# User_Interface.net
KiCad netlist of a schematic drawn in Altium Designer
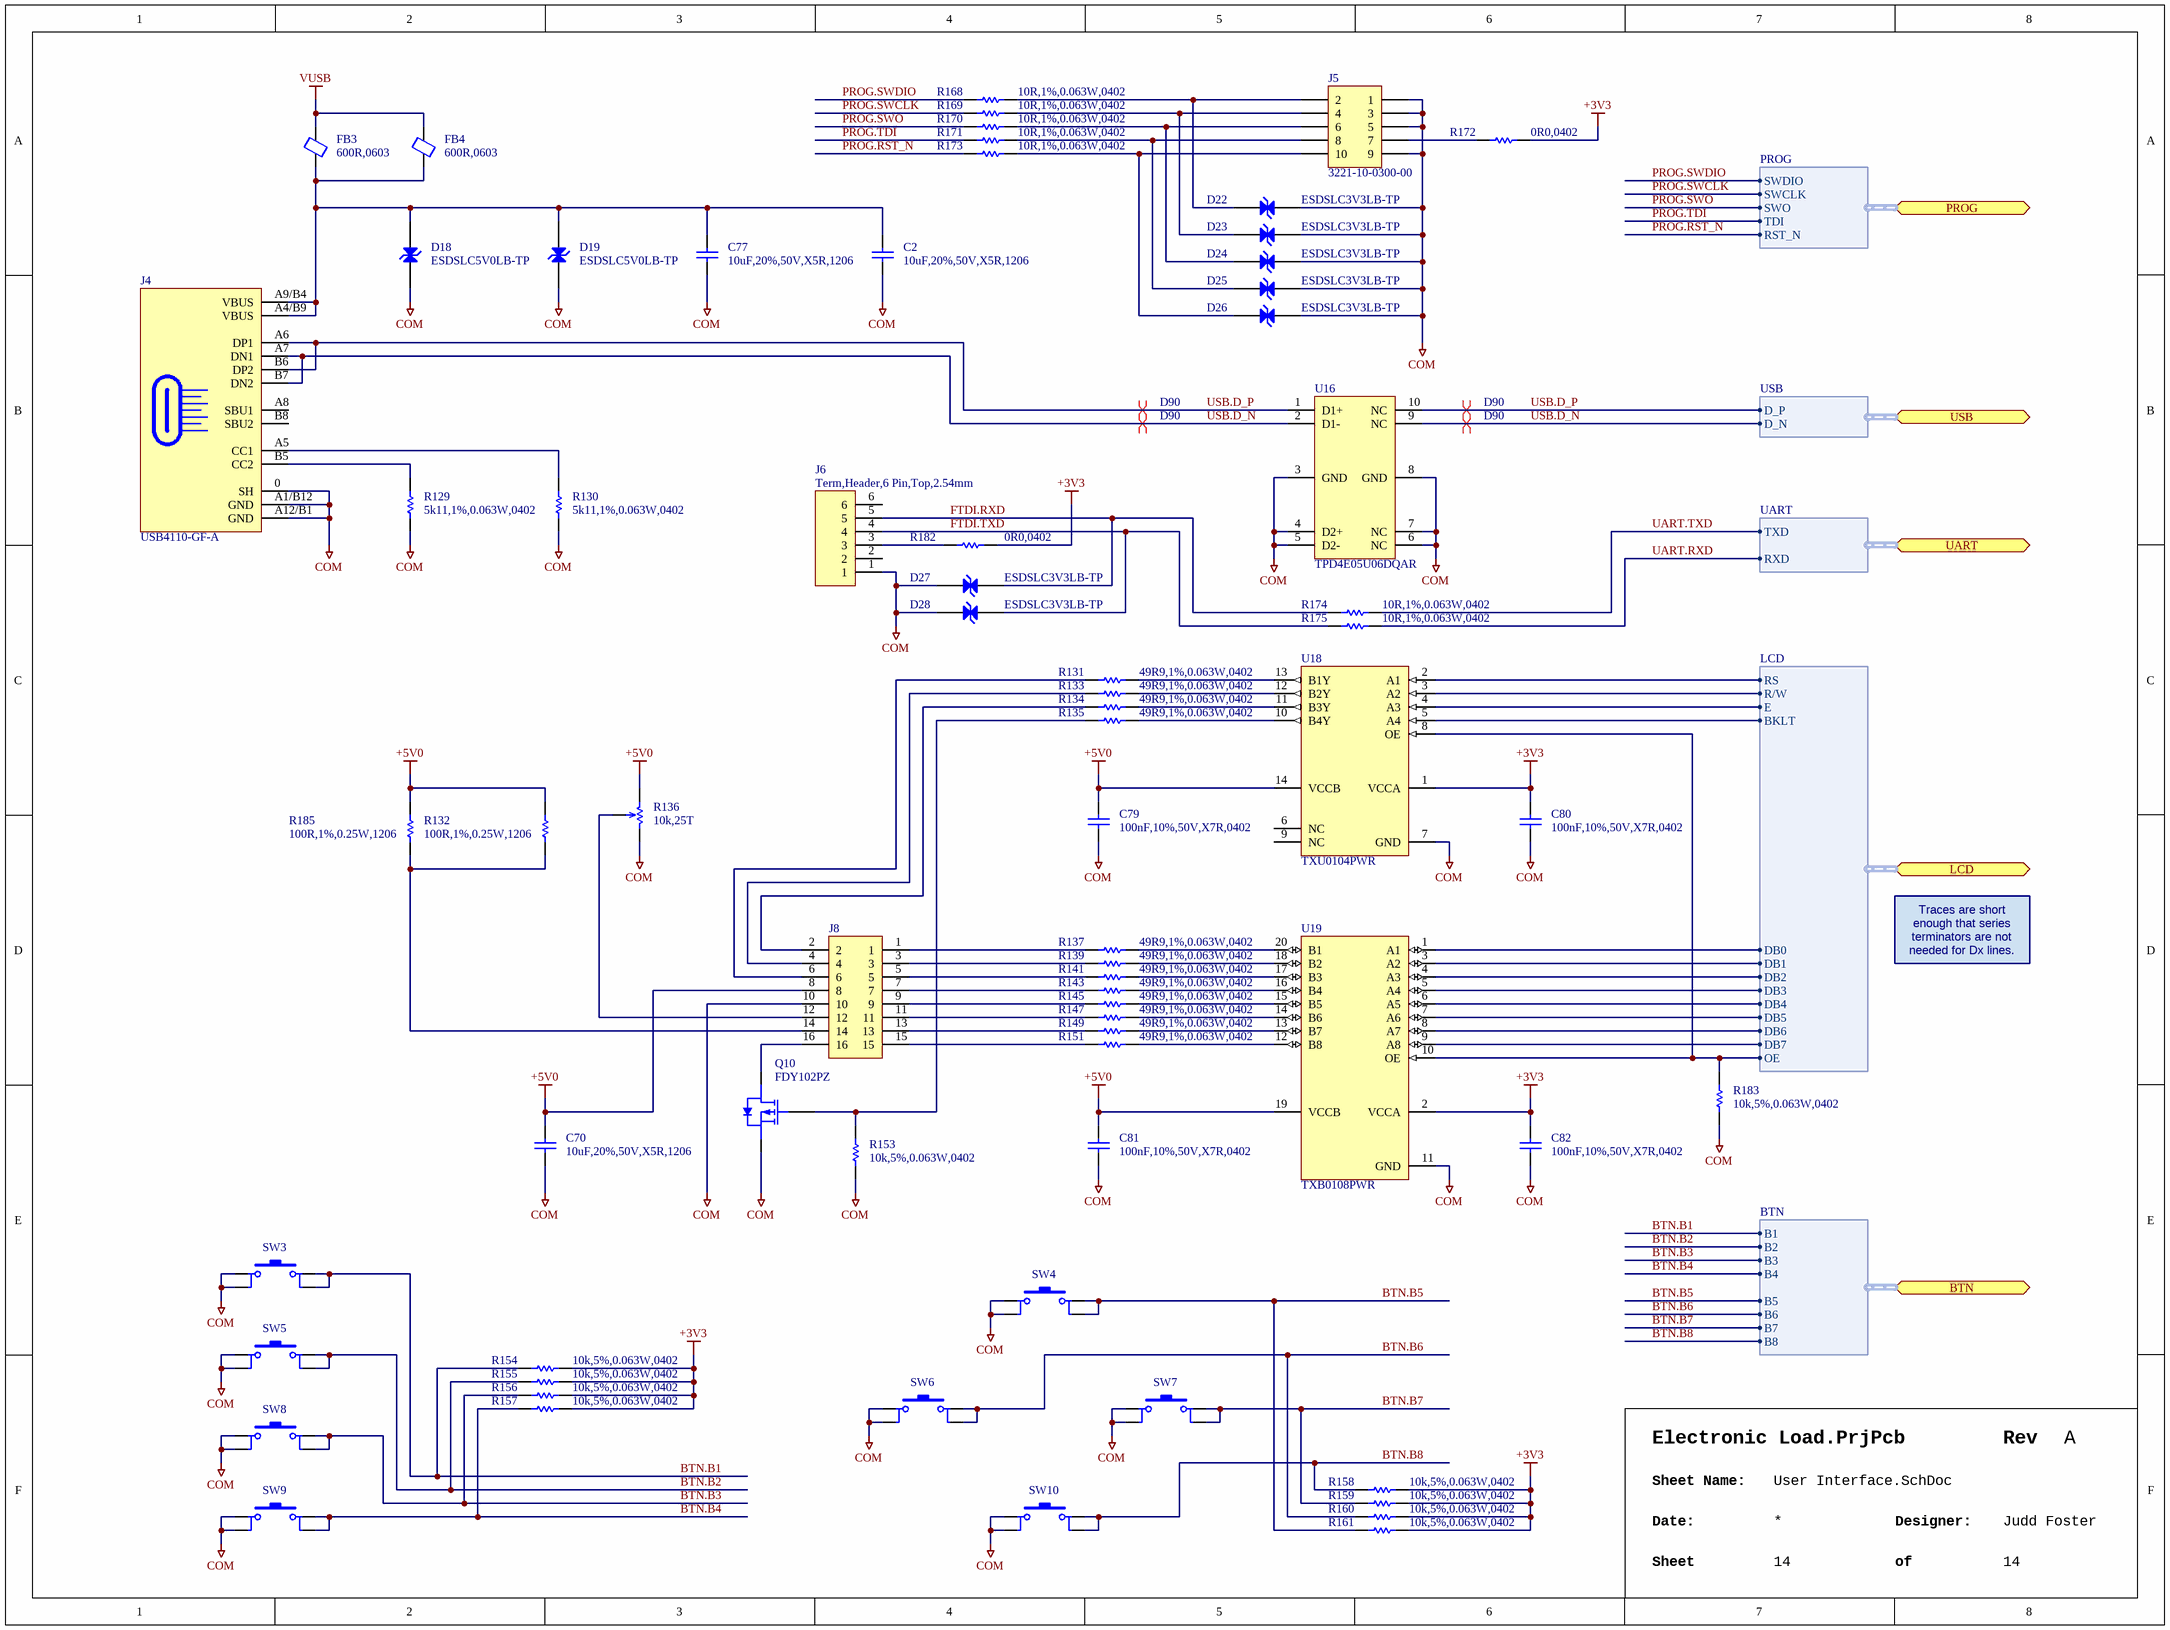
[diagram p0: User Interface.SchDoc]

(export (version "E")
  (design (tool "Eeschema 10.0.6"))
  (components
    (comp (ref "C2")
      (value "10uF,20%,50V,X5R,1206")
      (footprint "CAPC3216X16N")
      (description "10ï¿½F ï¿½20% 50V Ceramic Capacitor X5R 1206 (3216 Metric)")
      (fields
        (field (name "MANUFACTURER 1 PART NUMBER") "CL31A106MBHNNNE")
        (field (name "VENDOR 1 PART NUMBER") "1276-6736-1-ND")
        (field (name "CREATEDBY") "Judd Foster")
      )
      (libsource (lib "Component Library") (part "CAP,Cer,10uF,50VDC,X5R,1206"))
    )
    (comp (ref "C70")
      (value "10uF,20%,50V,X5R,1206")
      (footprint "CAPC3216X16N")
      (description "10ï¿½F ï¿½20% 50V Ceramic Capacitor X5R 1206 (3216 Metric)")
      (fields
        (field (name "MANUFACTURER 1 PART NUMBER") "CL31A106MBHNNNE")
        (field (name "VENDOR 1 PART NUMBER") "1276-6736-1-ND")
        (field (name "CREATEDBY") "Judd Foster")
      )
      (libsource (lib "Component Library") (part "CAP,Cer,10uF,50VDC,X5R,1206"))
    )
    (comp (ref "C77")
      (value "10uF,20%,50V,X5R,1206")
      (footprint "CAPC3216X16N")
      (description "10ï¿½F ï¿½20% 50V Ceramic Capacitor X5R 1206 (3216 Metric)")
      (fields
        (field (name "MANUFACTURER 1 PART NUMBER") "CL31A106MBHNNNE")
        (field (name "VENDOR 1 PART NUMBER") "1276-6736-1-ND")
        (field (name "CREATEDBY") "Judd Foster")
      )
      (libsource (lib "Component Library") (part "CAP,Cer,10uF,50VDC,X5R,1206"))
    )
    (comp (ref "C79")
      (value "100nF,10%,50V,X7R,0402")
      (footprint "CAPC1005X06N")
      (description "50V 100nF X7R Â±10% 0402 Ceramic Capacitors ROHS")
      (fields
        (field (name "MANUFACTURER 1 PART NUMBER") "GRM155R71H104KE14D")
        (field (name "VENDOR 1 PART NUMBER") "C77020")
        (field (name "CREATEDBY") "Judd Foster")
      )
      (libsource (lib "Component Library") (part "CAP,NPOL"))
    )
    (comp (ref "C80")
      (value "100nF,10%,50V,X7R,0402")
      (footprint "CAPC1005X06N")
      (description "50V 100nF X7R Â±10% 0402 Ceramic Capacitors ROHS")
      (fields
        (field (name "MANUFACTURER 1 PART NUMBER") "GRM155R71H104KE14D")
        (field (name "VENDOR 1 PART NUMBER") "C77020")
        (field (name "CREATEDBY") "Judd Foster")
      )
      (libsource (lib "Component Library") (part "CAP,NPOL"))
    )
    (comp (ref "C81")
      (value "100nF,10%,50V,X7R,0402")
      (footprint "CAPC1005X06N")
      (description "50V 100nF X7R Â±10% 0402 Ceramic Capacitors ROHS")
      (fields
        (field (name "MANUFACTURER 1 PART NUMBER") "GRM155R71H104KE14D")
        (field (name "VENDOR 1 PART NUMBER") "C77020")
        (field (name "CREATEDBY") "Judd Foster")
      )
      (libsource (lib "Component Library") (part "CAP,NPOL"))
    )
    (comp (ref "C82")
      (value "100nF,10%,50V,X7R,0402")
      (footprint "CAPC1005X06N")
      (description "50V 100nF X7R Â±10% 0402 Ceramic Capacitors ROHS")
      (fields
        (field (name "MANUFACTURER 1 PART NUMBER") "GRM155R71H104KE14D")
        (field (name "VENDOR 1 PART NUMBER") "C77020")
        (field (name "CREATEDBY") "Judd Foster")
      )
      (libsource (lib "Component Library") (part "CAP,NPOL"))
    )
    (comp (ref "D18")
      (value "ESDSLC5V0LB-TP")
      (footprint "MICROCOMMERCIAL_DFN1006-2_NPOL")
      (description "20V Clamp 4A (8/20ï¿½s) Ipp Tvs Diode Surface Mount 2-DFN1006")
      (fields
        (field (name "VENDOR 1 PART NUMBER") "ESDSLC5V0LB-TPMSCT-ND")
        (field (name "CREATEDBY") "Judd Foster")
      )
      (libsource (lib "Component Library") (part "DIODE,TVS,5.0V,SOD882"))
    )
    (comp (ref "D19")
      (value "ESDSLC5V0LB-TP")
      (footprint "MICROCOMMERCIAL_DFN1006-2_NPOL")
      (description "20V Clamp 4A (8/20ï¿½s) Ipp Tvs Diode Surface Mount 2-DFN1006")
      (fields
        (field (name "VENDOR 1 PART NUMBER") "ESDSLC5V0LB-TPMSCT-ND")
        (field (name "CREATEDBY") "Judd Foster")
      )
      (libsource (lib "Component Library") (part "DIODE,TVS,5.0V,SOD882"))
    )
    (comp (ref "D22")
      (value "ESDSLC3V3LB-TP")
      (footprint "DFN65P100X50-2N")
      (description "20V Clamp 5A (8/20ï¿½s) Ipp Tvs Diode Surface Mount DFN1006-2")
      (fields
        (field (name "VENDOR 1 PART NUMBER") "ESDSLC3V3LB-TPMSCT-ND")
        (field (name "CREATEDBY") "Judd Foster")
      )
      (libsource (lib "Component Library") (part "DIODE,TVS,3.3V,SOD882"))
    )
    (comp (ref "D23")
      (value "ESDSLC3V3LB-TP")
      (footprint "DFN65P100X50-2N")
      (description "20V Clamp 5A (8/20ï¿½s) Ipp Tvs Diode Surface Mount DFN1006-2")
      (fields
        (field (name "VENDOR 1 PART NUMBER") "ESDSLC3V3LB-TPMSCT-ND")
        (field (name "CREATEDBY") "Judd Foster")
      )
      (libsource (lib "Component Library") (part "DIODE,TVS,3.3V,SOD882"))
    )
    (comp (ref "D24")
      (value "ESDSLC3V3LB-TP")
      (footprint "DFN65P100X50-2N")
      (description "20V Clamp 5A (8/20ï¿½s) Ipp Tvs Diode Surface Mount DFN1006-2")
      (fields
        (field (name "VENDOR 1 PART NUMBER") "ESDSLC3V3LB-TPMSCT-ND")
        (field (name "CREATEDBY") "Judd Foster")
      )
      (libsource (lib "Component Library") (part "DIODE,TVS,3.3V,SOD882"))
    )
    (comp (ref "D25")
      (value "ESDSLC3V3LB-TP")
      (footprint "DFN65P100X50-2N")
      (description "20V Clamp 5A (8/20ï¿½s) Ipp Tvs Diode Surface Mount DFN1006-2")
      (fields
        (field (name "VENDOR 1 PART NUMBER") "ESDSLC3V3LB-TPMSCT-ND")
        (field (name "CREATEDBY") "Judd Foster")
      )
      (libsource (lib "Component Library") (part "DIODE,TVS,3.3V,SOD882"))
    )
    (comp (ref "D26")
      (value "ESDSLC3V3LB-TP")
      (footprint "DFN65P100X50-2N")
      (description "20V Clamp 5A (8/20ï¿½s) Ipp Tvs Diode Surface Mount DFN1006-2")
      (fields
        (field (name "VENDOR 1 PART NUMBER") "ESDSLC3V3LB-TPMSCT-ND")
        (field (name "CREATEDBY") "Judd Foster")
      )
      (libsource (lib "Component Library") (part "DIODE,TVS,3.3V,SOD882"))
    )
    (comp (ref "D27")
      (value "ESDSLC3V3LB-TP")
      (footprint "DFN65P100X50-2N")
      (description "20V Clamp 5A (8/20ï¿½s) Ipp Tvs Diode Surface Mount DFN1006-2")
      (fields
        (field (name "VENDOR 1 PART NUMBER") "ESDSLC3V3LB-TPMSCT-ND")
        (field (name "CREATEDBY") "Judd Foster")
      )
      (libsource (lib "Component Library") (part "DIODE,TVS,3.3V,SOD882"))
    )
    (comp (ref "D28")
      (value "ESDSLC3V3LB-TP")
      (footprint "DFN65P100X50-2N")
      (description "20V Clamp 5A (8/20ï¿½s) Ipp Tvs Diode Surface Mount DFN1006-2")
      (fields
        (field (name "VENDOR 1 PART NUMBER") "ESDSLC3V3LB-TPMSCT-ND")
        (field (name "CREATEDBY") "Judd Foster")
      )
      (libsource (lib "Component Library") (part "DIODE,TVS,3.3V,SOD882"))
    )
    (comp (ref "FB3")
      (value "600R,0603")
      (footprint "INDC_0603")
      (description "500mÎ© Â±25% 600Î©@100MHz 0603 Ferrite Beads and Chips ROHS")
      (fields
        (field (name "MANUFACTURER 1 PART NUMBER") "FCM1608KF-601T03")
        (field (name "VENDOR 1 PART NUMBER") "C141723")
        (field (name "CREATEDBY") "Judd Foster")
      )
      (libsource (lib "Component Library") (part "FERRITE"))
    )
    (comp (ref "FB4")
      (value "600R,0603")
      (footprint "INDC_0603")
      (description "500mÎ© Â±25% 600Î©@100MHz 0603 Ferrite Beads and Chips ROHS")
      (fields
        (field (name "MANUFACTURER 1 PART NUMBER") "FCM1608KF-601T03")
        (field (name "VENDOR 1 PART NUMBER") "C141723")
        (field (name "CREATEDBY") "Judd Foster")
      )
      (libsource (lib "Component Library") (part "FERRITE"))
    )
    (comp (ref "J4")
      (value "USB4110-GF-A")
      (footprint "GCT_USB4110-GF-A")
      (fields
        (field (name "VENDOR 1 PART NUMBER") "2073-USB4110-GF-A-1-ND")
        (field (name "CREATEDBY") "Judd Foster")
      )
      (libsource (lib "Component Library") (part "Conn,USB-C,SMD"))
    )
    (comp (ref "J5")
      (value "3221-10-0300-00")
      (footprint "CNC Tech_3221-10-0300-00")
      (description "Connector Header Surface Mount 10 position 0.050\" (1.27mm)")
      (fields (field (name "VENDOR 1 PART NUMBER") "1175-1735-ND") (field (name "CREATEDBY") "Judd Foster"))
      (libsource (lib "Component Library") (part "Term,Header,5x2 Pin,Shroud,1.27mm,SMD"))
    )
    (comp (ref "J6")
      (value "Term,Header,6 Pin,Top,2.54mm")
      (footprint "WURTH_61300611121")
      (description "Connector Header Through Hole 6 position 0.100\" (2.54mm)")
      (fields
        (field (name "MANUFACTURER 1 PART NUMBER") "61300611121")
        (field (name "VENDOR 1 PART NUMBER") "732-5319-ND")
        (field (name "CREATEDBY") "Judd Foster")
      )
      (libsource (lib "Component Library") (part "Term,Header,6 Pin,Top,2.54mm"))
    )
    (comp (ref "J8")
      (value "PPPC082LFBN-RC")
      (footprint "SULLINS_PPPC082LFBN-RC")
      (description "16 Position Header Connector 0.100\" (2.54mm) Through Hole Gold")
      (fields (field (name "VENDOR 1 PART NUMBER") "S7111-ND") (field (name "CREATEDBY") "Judd Foster"))
      (libsource (lib "Component Library") (part "Term,Rcpt,2x8 Pin,2.54mm,Top,Thru"))
    )
    (comp (ref "Q10")
      (value "FDY102PZ")
      (footprint "ONSEMI_SC-89")
      (description "P-Channel 20 V 830mA (Ta) 625mW (Ta) Surface Mount SC-89-3")
      (fields (field (name "VENDOR 1 PART NUMBER") "FDY102PZCT-ND") (field (name "CREATEDBY") "Judd Foster"))
      (libsource (lib "Component Library") (part "MOSFET,P Ch,20V,830mA"))
    )
    (comp (ref "R129")
      (value "5k11,1%,0.063W,0402")
      (footprint "RESC1005X04N")
      (fields
        (field (name "MANUFACTURER 1 PART NUMBER") "AC0402FR-075K11L")
        (field (name "VENDOR 1 PART NUMBER") "13-AC0402FR-075K11LCT-ND")
        (field (name "CREATEDBY") "Judd Foster")
      )
      (libsource (lib "Component Library") (part "RES,5k11,1%,0.063W,0402"))
    )
    (comp (ref "R130")
      (value "5k11,1%,0.063W,0402")
      (footprint "RESC1005X04N")
      (fields
        (field (name "MANUFACTURER 1 PART NUMBER") "AC0402FR-075K11L")
        (field (name "VENDOR 1 PART NUMBER") "13-AC0402FR-075K11LCT-ND")
        (field (name "CREATEDBY") "Judd Foster")
      )
      (libsource (lib "Component Library") (part "RES,5k11,1%,0.063W,0402"))
    )
    (comp (ref "R131")
      (value "49R9,1%,0.063W,0402")
      (footprint "RESC1005X04N")
      (description "49.9 Ohms Â±1% 0.063W, 1/16W Chip Resistor 0402 (1005 Metric) Moisture Resistant Thick Film")
      (fields
        (field (name "MANUFACTURER 1 PART NUMBER") "RC0402FR-0749R9L")
        (field (name "VENDOR 1 PART NUMBER") "311-49.9LRCT-ND")
        (field (name "CREATEDBY") "Judd Foster")
      )
      (libsource (lib "Component Library") (part "RES,49R9,1%,0.063W,0402"))
    )
    (comp (ref "R132")
      (value "100R,1%,0.25W,1206")
      (footprint "SEI_PKG_RMCF1206")
      (description "100 Ohms Â±1% 0.25W, 1/4W Chip Resistor 1206 (3216 Metric) Automotive AEC-Q200 Thick Film")
      (fields
        (field (name "MANUFACTURER 1 PART NUMBER") "RMCF1206FT100R")
        (field (name "VENDOR 1 PART NUMBER") "RMCF1206FT100RCT-ND")
        (field (name "CREATEDBY") "Judd Foster")
      )
      (libsource (lib "Component Library") (part "RES,100R,1%,0.25W,1206"))
    )
    (comp (ref "R133")
      (value "49R9,1%,0.063W,0402")
      (footprint "RESC1005X04N")
      (description "49.9 Ohms Â±1% 0.063W, 1/16W Chip Resistor 0402 (1005 Metric) Moisture Resistant Thick Film")
      (fields
        (field (name "MANUFACTURER 1 PART NUMBER") "RC0402FR-0749R9L")
        (field (name "VENDOR 1 PART NUMBER") "311-49.9LRCT-ND")
        (field (name "CREATEDBY") "Judd Foster")
      )
      (libsource (lib "Component Library") (part "RES,49R9,1%,0.063W,0402"))
    )
    (comp (ref "R134")
      (value "49R9,1%,0.063W,0402")
      (footprint "RESC1005X04N")
      (description "49.9 Ohms Â±1% 0.063W, 1/16W Chip Resistor 0402 (1005 Metric) Moisture Resistant Thick Film")
      (fields
        (field (name "MANUFACTURER 1 PART NUMBER") "RC0402FR-0749R9L")
        (field (name "VENDOR 1 PART NUMBER") "311-49.9LRCT-ND")
        (field (name "CREATEDBY") "Judd Foster")
      )
      (libsource (lib "Component Library") (part "RES,49R9,1%,0.063W,0402"))
    )
    (comp (ref "R135")
      (value "49R9,1%,0.063W,0402")
      (footprint "RESC1005X04N")
      (description "49.9 Ohms Â±1% 0.063W, 1/16W Chip Resistor 0402 (1005 Metric) Moisture Resistant Thick Film")
      (fields
        (field (name "MANUFACTURER 1 PART NUMBER") "RC0402FR-0749R9L")
        (field (name "VENDOR 1 PART NUMBER") "311-49.9LRCT-ND")
        (field (name "CREATEDBY") "Judd Foster")
      )
      (libsource (lib "Component Library") (part "RES,49R9,1%,0.063W,0402"))
    )
    (comp (ref "R136")
      (value "10k,25T")
      (footprint "BOURNS_3296W")
      (description "Â±10% Â±100ppm/â„ƒ 500mW 10kÎ© SIP-3P,9.5x4.8mm Trimmer Potentiometers ROHS")
      (fields
        (field (name "MANUFACTURER 1 PART NUMBER") "3296W-1-103LF")
        (field (name "VENDOR 1 PART NUMBER") "C34846")
        (field (name "CREATEDBY") "Judd Foster")
      )
      (libsource (lib "Component Library") (part "RES,TRIM"))
    )
    (comp (ref "R137")
      (value "49R9,1%,0.063W,0402")
      (footprint "RESC1005X04N")
      (description "49.9 Ohms Â±1% 0.063W, 1/16W Chip Resistor 0402 (1005 Metric) Moisture Resistant Thick Film")
      (fields
        (field (name "MANUFACTURER 1 PART NUMBER") "RC0402FR-0749R9L")
        (field (name "VENDOR 1 PART NUMBER") "311-49.9LRCT-ND")
        (field (name "CREATEDBY") "Judd Foster")
      )
      (libsource (lib "Component Library") (part "RES,49R9,1%,0.063W,0402"))
    )
    (comp (ref "R139")
      (value "49R9,1%,0.063W,0402")
      (footprint "RESC1005X04N")
      (description "49.9 Ohms Â±1% 0.063W, 1/16W Chip Resistor 0402 (1005 Metric) Moisture Resistant Thick Film")
      (fields
        (field (name "MANUFACTURER 1 PART NUMBER") "RC0402FR-0749R9L")
        (field (name "VENDOR 1 PART NUMBER") "311-49.9LRCT-ND")
        (field (name "CREATEDBY") "Judd Foster")
      )
      (libsource (lib "Component Library") (part "RES,49R9,1%,0.063W,0402"))
    )
    (comp (ref "R141")
      (value "49R9,1%,0.063W,0402")
      (footprint "RESC1005X04N")
      (description "49.9 Ohms Â±1% 0.063W, 1/16W Chip Resistor 0402 (1005 Metric) Moisture Resistant Thick Film")
      (fields
        (field (name "MANUFACTURER 1 PART NUMBER") "RC0402FR-0749R9L")
        (field (name "VENDOR 1 PART NUMBER") "311-49.9LRCT-ND")
        (field (name "CREATEDBY") "Judd Foster")
      )
      (libsource (lib "Component Library") (part "RES,49R9,1%,0.063W,0402"))
    )
    (comp (ref "R143")
      (value "49R9,1%,0.063W,0402")
      (footprint "RESC1005X04N")
      (description "49.9 Ohms Â±1% 0.063W, 1/16W Chip Resistor 0402 (1005 Metric) Moisture Resistant Thick Film")
      (fields
        (field (name "MANUFACTURER 1 PART NUMBER") "RC0402FR-0749R9L")
        (field (name "VENDOR 1 PART NUMBER") "311-49.9LRCT-ND")
        (field (name "CREATEDBY") "Judd Foster")
      )
      (libsource (lib "Component Library") (part "RES,49R9,1%,0.063W,0402"))
    )
    (comp (ref "R145")
      (value "49R9,1%,0.063W,0402")
      (footprint "RESC1005X04N")
      (description "49.9 Ohms Â±1% 0.063W, 1/16W Chip Resistor 0402 (1005 Metric) Moisture Resistant Thick Film")
      (fields
        (field (name "MANUFACTURER 1 PART NUMBER") "RC0402FR-0749R9L")
        (field (name "VENDOR 1 PART NUMBER") "311-49.9LRCT-ND")
        (field (name "CREATEDBY") "Judd Foster")
      )
      (libsource (lib "Component Library") (part "RES,49R9,1%,0.063W,0402"))
    )
    (comp (ref "R147")
      (value "49R9,1%,0.063W,0402")
      (footprint "RESC1005X04N")
      (description "49.9 Ohms Â±1% 0.063W, 1/16W Chip Resistor 0402 (1005 Metric) Moisture Resistant Thick Film")
      (fields
        (field (name "MANUFACTURER 1 PART NUMBER") "RC0402FR-0749R9L")
        (field (name "VENDOR 1 PART NUMBER") "311-49.9LRCT-ND")
        (field (name "CREATEDBY") "Judd Foster")
      )
      (libsource (lib "Component Library") (part "RES,49R9,1%,0.063W,0402"))
    )
    (comp (ref "R149")
      (value "49R9,1%,0.063W,0402")
      (footprint "RESC1005X04N")
      (description "49.9 Ohms Â±1% 0.063W, 1/16W Chip Resistor 0402 (1005 Metric) Moisture Resistant Thick Film")
      (fields
        (field (name "MANUFACTURER 1 PART NUMBER") "RC0402FR-0749R9L")
        (field (name "VENDOR 1 PART NUMBER") "311-49.9LRCT-ND")
        (field (name "CREATEDBY") "Judd Foster")
      )
      (libsource (lib "Component Library") (part "RES,49R9,1%,0.063W,0402"))
    )
    (comp (ref "R151")
      (value "49R9,1%,0.063W,0402")
      (footprint "RESC1005X04N")
      (description "49.9 Ohms Â±1% 0.063W, 1/16W Chip Resistor 0402 (1005 Metric) Moisture Resistant Thick Film")
      (fields
        (field (name "MANUFACTURER 1 PART NUMBER") "RC0402FR-0749R9L")
        (field (name "VENDOR 1 PART NUMBER") "311-49.9LRCT-ND")
        (field (name "CREATEDBY") "Judd Foster")
      )
      (libsource (lib "Component Library") (part "RES,49R9,1%,0.063W,0402"))
    )
    (comp (ref "R153")
      (value "10k,5%,0.063W,0402")
      (footprint "RESC1005X04N")
      (description "10 kOhms ï¿½5% 0.063W, 1/16W Chip Resistor 0402 (1005 Metric) Automotive AEC-Q200 Thick Film")
      (fields
        (field (name "MANUFACTURER 1 PART NUMBER") "RMCF0402JT10K0")
        (field (name "VENDOR 1 PART NUMBER") "RMCF0402JT10K0CT-ND")
        (field (name "CREATEDBY") "Judd Foster")
      )
      (libsource (lib "Component Library") (part "RES,10k,5%,0.063W,0402"))
    )
    (comp (ref "R154")
      (value "10k,5%,0.063W,0402")
      (footprint "RESC1005X04N")
      (description "10 kOhms ï¿½5% 0.063W, 1/16W Chip Resistor 0402 (1005 Metric) Automotive AEC-Q200 Thick Film")
      (fields
        (field (name "MANUFACTURER 1 PART NUMBER") "RMCF0402JT10K0")
        (field (name "VENDOR 1 PART NUMBER") "RMCF0402JT10K0CT-ND")
        (field (name "CREATEDBY") "Judd Foster")
      )
      (libsource (lib "Component Library") (part "RES,10k,5%,0.063W,0402"))
    )
    (comp (ref "R155")
      (value "10k,5%,0.063W,0402")
      (footprint "RESC1005X04N")
      (description "10 kOhms ï¿½5% 0.063W, 1/16W Chip Resistor 0402 (1005 Metric) Automotive AEC-Q200 Thick Film")
      (fields
        (field (name "MANUFACTURER 1 PART NUMBER") "RMCF0402JT10K0")
        (field (name "VENDOR 1 PART NUMBER") "RMCF0402JT10K0CT-ND")
        (field (name "CREATEDBY") "Judd Foster")
      )
      (libsource (lib "Component Library") (part "RES,10k,5%,0.063W,0402"))
    )
    (comp (ref "R156")
      (value "10k,5%,0.063W,0402")
      (footprint "RESC1005X04N")
      (description "10 kOhms ï¿½5% 0.063W, 1/16W Chip Resistor 0402 (1005 Metric) Automotive AEC-Q200 Thick Film")
      (fields
        (field (name "MANUFACTURER 1 PART NUMBER") "RMCF0402JT10K0")
        (field (name "VENDOR 1 PART NUMBER") "RMCF0402JT10K0CT-ND")
        (field (name "CREATEDBY") "Judd Foster")
      )
      (libsource (lib "Component Library") (part "RES,10k,5%,0.063W,0402"))
    )
    (comp (ref "R157")
      (value "10k,5%,0.063W,0402")
      (footprint "RESC1005X04N")
      (description "10 kOhms ï¿½5% 0.063W, 1/16W Chip Resistor 0402 (1005 Metric) Automotive AEC-Q200 Thick Film")
      (fields
        (field (name "MANUFACTURER 1 PART NUMBER") "RMCF0402JT10K0")
        (field (name "VENDOR 1 PART NUMBER") "RMCF0402JT10K0CT-ND")
        (field (name "CREATEDBY") "Judd Foster")
      )
      (libsource (lib "Component Library") (part "RES,10k,5%,0.063W,0402"))
    )
    (comp (ref "R158")
      (value "10k,5%,0.063W,0402")
      (footprint "RESC1005X04N")
      (description "10 kOhms ï¿½5% 0.063W, 1/16W Chip Resistor 0402 (1005 Metric) Automotive AEC-Q200 Thick Film")
      (fields
        (field (name "MANUFACTURER 1 PART NUMBER") "RMCF0402JT10K0")
        (field (name "VENDOR 1 PART NUMBER") "RMCF0402JT10K0CT-ND")
        (field (name "CREATEDBY") "Judd Foster")
      )
      (libsource (lib "Component Library") (part "RES,10k,5%,0.063W,0402"))
    )
    (comp (ref "R159")
      (value "10k,5%,0.063W,0402")
      (footprint "RESC1005X04N")
      (description "10 kOhms ï¿½5% 0.063W, 1/16W Chip Resistor 0402 (1005 Metric) Automotive AEC-Q200 Thick Film")
      (fields
        (field (name "MANUFACTURER 1 PART NUMBER") "RMCF0402JT10K0")
        (field (name "VENDOR 1 PART NUMBER") "RMCF0402JT10K0CT-ND")
        (field (name "CREATEDBY") "Judd Foster")
      )
      (libsource (lib "Component Library") (part "RES,10k,5%,0.063W,0402"))
    )
    (comp (ref "R160")
      (value "10k,5%,0.063W,0402")
      (footprint "RESC1005X04N")
      (description "10 kOhms ï¿½5% 0.063W, 1/16W Chip Resistor 0402 (1005 Metric) Automotive AEC-Q200 Thick Film")
      (fields
        (field (name "MANUFACTURER 1 PART NUMBER") "RMCF0402JT10K0")
        (field (name "VENDOR 1 PART NUMBER") "RMCF0402JT10K0CT-ND")
        (field (name "CREATEDBY") "Judd Foster")
      )
      (libsource (lib "Component Library") (part "RES,10k,5%,0.063W,0402"))
    )
    (comp (ref "R161")
      (value "10k,5%,0.063W,0402")
      (footprint "RESC1005X04N")
      (description "10 kOhms ï¿½5% 0.063W, 1/16W Chip Resistor 0402 (1005 Metric) Automotive AEC-Q200 Thick Film")
      (fields
        (field (name "MANUFACTURER 1 PART NUMBER") "RMCF0402JT10K0")
        (field (name "VENDOR 1 PART NUMBER") "RMCF0402JT10K0CT-ND")
        (field (name "CREATEDBY") "Judd Foster")
      )
      (libsource (lib "Component Library") (part "RES,10k,5%,0.063W,0402"))
    )
    (comp (ref "R168")
      (value "10R,1%,0.063W,0402")
      (footprint "RESC1005X04N")
      (description "10 Ohms ï¿½1% 0.063W, 1/16W Chip Resistor 0402 (1005 Metric) Automotive AEC-Q200 Thick Film")
      (fields
        (field (name "MANUFACTURER 1 PART NUMBER") "ERJ-2RKF10R0X")
        (field (name "VENDOR 1 PART NUMBER") "P10.0LCT-ND")
        (field (name "CREATEDBY") "Judd Foster")
      )
      (libsource (lib "Component Library") (part "RES,10R,1%,0.063W,0402"))
    )
    (comp (ref "R169")
      (value "10R,1%,0.063W,0402")
      (footprint "RESC1005X04N")
      (description "10 Ohms ï¿½1% 0.063W, 1/16W Chip Resistor 0402 (1005 Metric) Automotive AEC-Q200 Thick Film")
      (fields
        (field (name "MANUFACTURER 1 PART NUMBER") "ERJ-2RKF10R0X")
        (field (name "VENDOR 1 PART NUMBER") "P10.0LCT-ND")
        (field (name "CREATEDBY") "Judd Foster")
      )
      (libsource (lib "Component Library") (part "RES,10R,1%,0.063W,0402"))
    )
    (comp (ref "R170")
      (value "10R,1%,0.063W,0402")
      (footprint "RESC1005X04N")
      (description "10 Ohms ï¿½1% 0.063W, 1/16W Chip Resistor 0402 (1005 Metric) Automotive AEC-Q200 Thick Film")
      (fields
        (field (name "MANUFACTURER 1 PART NUMBER") "ERJ-2RKF10R0X")
        (field (name "VENDOR 1 PART NUMBER") "P10.0LCT-ND")
        (field (name "CREATEDBY") "Judd Foster")
      )
      (libsource (lib "Component Library") (part "RES,10R,1%,0.063W,0402"))
    )
    (comp (ref "R171")
      (value "10R,1%,0.063W,0402")
      (footprint "RESC1005X04N")
      (description "10 Ohms ï¿½1% 0.063W, 1/16W Chip Resistor 0402 (1005 Metric) Automotive AEC-Q200 Thick Film")
      (fields
        (field (name "MANUFACTURER 1 PART NUMBER") "ERJ-2RKF10R0X")
        (field (name "VENDOR 1 PART NUMBER") "P10.0LCT-ND")
        (field (name "CREATEDBY") "Judd Foster")
      )
      (libsource (lib "Component Library") (part "RES,10R,1%,0.063W,0402"))
    )
    (comp (ref "R172")
      (value "0R0,0402")
      (footprint "RESC1005X04N")
      (description "0 Ohms Jumper 0.1W, 1/10W Chip Resistor 0402 (1005 Metric) Automotive AEC-Q200 Thick Film")
      (fields
        (field (name "MANUFACTURER 1 PART NUMBER") "ERJ-2GE0R00X")
        (field (name "VENDOR 1 PART NUMBER") "P0.0JCT-ND")
        (field (name "CREATEDBY") "Judd Foster")
      )
      (libsource (lib "Component Library") (part "RES,0R0,0402"))
    )
    (comp (ref "R173")
      (value "10R,1%,0.063W,0402")
      (footprint "RESC1005X04N")
      (description "10 Ohms ï¿½1% 0.063W, 1/16W Chip Resistor 0402 (1005 Metric) Automotive AEC-Q200 Thick Film")
      (fields
        (field (name "MANUFACTURER 1 PART NUMBER") "ERJ-2RKF10R0X")
        (field (name "VENDOR 1 PART NUMBER") "P10.0LCT-ND")
        (field (name "CREATEDBY") "Judd Foster")
      )
      (libsource (lib "Component Library") (part "RES,10R,1%,0.063W,0402"))
    )
    (comp (ref "R174")
      (value "10R,1%,0.063W,0402")
      (footprint "RESC1005X04N")
      (description "10 Ohms ï¿½1% 0.063W, 1/16W Chip Resistor 0402 (1005 Metric) Automotive AEC-Q200 Thick Film")
      (fields
        (field (name "MANUFACTURER 1 PART NUMBER") "ERJ-2RKF10R0X")
        (field (name "VENDOR 1 PART NUMBER") "P10.0LCT-ND")
        (field (name "CREATEDBY") "Judd Foster")
      )
      (libsource (lib "Component Library") (part "RES,10R,1%,0.063W,0402"))
    )
    (comp (ref "R175")
      (value "10R,1%,0.063W,0402")
      (footprint "RESC1005X04N")
      (description "10 Ohms ï¿½1% 0.063W, 1/16W Chip Resistor 0402 (1005 Metric) Automotive AEC-Q200 Thick Film")
      (fields
        (field (name "MANUFACTURER 1 PART NUMBER") "ERJ-2RKF10R0X")
        (field (name "VENDOR 1 PART NUMBER") "P10.0LCT-ND")
        (field (name "CREATEDBY") "Judd Foster")
      )
      (libsource (lib "Component Library") (part "RES,10R,1%,0.063W,0402"))
    )
    (comp (ref "R182")
      (value "0R0,0402")
      (footprint "RESC1005X04N")
      (description "0 Ohms Jumper 0.1W, 1/10W Chip Resistor 0402 (1005 Metric) Automotive AEC-Q200 Thick Film")
      (fields
        (field (name "MANUFACTURER 1 PART NUMBER") "ERJ-2GE0R00X")
        (field (name "VENDOR 1 PART NUMBER") "P0.0JCT-ND")
        (field (name "CREATEDBY") "Judd Foster")
      )
      (libsource (lib "Component Library") (part "RES,0R0,0402"))
    )
    (comp (ref "R183")
      (value "10k,5%,0.063W,0402")
      (footprint "RESC1005X04N")
      (description "10 kOhms ï¿½5% 0.063W, 1/16W Chip Resistor 0402 (1005 Metric) Automotive AEC-Q200 Thick Film")
      (fields
        (field (name "MANUFACTURER 1 PART NUMBER") "RMCF0402JT10K0")
        (field (name "VENDOR 1 PART NUMBER") "RMCF0402JT10K0CT-ND")
        (field (name "CREATEDBY") "Judd Foster")
      )
      (libsource (lib "Component Library") (part "RES,10k,5%,0.063W,0402"))
    )
    (comp (ref "R185")
      (value "100R,1%,0.25W,1206")
      (footprint "SEI_PKG_RMCF1206")
      (description "100 Ohms Â±1% 0.25W, 1/4W Chip Resistor 1206 (3216 Metric) Automotive AEC-Q200 Thick Film")
      (fields
        (field (name "MANUFACTURER 1 PART NUMBER") "RMCF1206FT100R")
        (field (name "VENDOR 1 PART NUMBER") "RMCF1206FT100RCT-ND")
        (field (name "CREATEDBY") "Judd Foster")
      )
      (libsource (lib "Component Library") (part "RES,100R,1%,0.25W,1206"))
    )
    (comp (ref "SW3")
      (value "PTS645SK43SMTR92 LFS")
      (footprint "C&K_PTS645SK43SMTR92 LFS")
      (description "Tactile Switch SPST-NO Top Actuated Surface Mount")
      (fields (field (name "VENDOR 1 PART NUMBER") "CKN9084CT-ND") (field (name "CREATEDBY") "Judd Foster"))
      (libsource (lib "Component Library") (part "Switch,Tactile,SPST-NO,SMD,H4.3"))
    )
    (comp (ref "SW4")
      (value "PTS645SK43SMTR92 LFS")
      (footprint "C&K_PTS645SK43SMTR92 LFS")
      (description "Tactile Switch SPST-NO Top Actuated Surface Mount")
      (fields (field (name "VENDOR 1 PART NUMBER") "CKN9084CT-ND") (field (name "CREATEDBY") "Judd Foster"))
      (libsource (lib "Component Library") (part "Switch,Tactile,SPST-NO,SMD,H4.3"))
    )
    (comp (ref "SW5")
      (value "PTS645SK43SMTR92 LFS")
      (footprint "C&K_PTS645SK43SMTR92 LFS")
      (description "Tactile Switch SPST-NO Top Actuated Surface Mount")
      (fields (field (name "VENDOR 1 PART NUMBER") "CKN9084CT-ND") (field (name "CREATEDBY") "Judd Foster"))
      (libsource (lib "Component Library") (part "Switch,Tactile,SPST-NO,SMD,H4.3"))
    )
    (comp (ref "SW6")
      (value "PTS645SK43SMTR92 LFS")
      (footprint "C&K_PTS645SK43SMTR92 LFS")
      (description "Tactile Switch SPST-NO Top Actuated Surface Mount")
      (fields (field (name "VENDOR 1 PART NUMBER") "CKN9084CT-ND") (field (name "CREATEDBY") "Judd Foster"))
      (libsource (lib "Component Library") (part "Switch,Tactile,SPST-NO,SMD,H4.3"))
    )
    (comp (ref "SW7")
      (value "PTS645SK43SMTR92 LFS")
      (footprint "C&K_PTS645SK43SMTR92 LFS")
      (description "Tactile Switch SPST-NO Top Actuated Surface Mount")
      (fields (field (name "VENDOR 1 PART NUMBER") "CKN9084CT-ND") (field (name "CREATEDBY") "Judd Foster"))
      (libsource (lib "Component Library") (part "Switch,Tactile,SPST-NO,SMD,H4.3"))
    )
    (comp (ref "SW8")
      (value "PTS645SK43SMTR92 LFS")
      (footprint "C&K_PTS645SK43SMTR92 LFS")
      (description "Tactile Switch SPST-NO Top Actuated Surface Mount")
      (fields (field (name "VENDOR 1 PART NUMBER") "CKN9084CT-ND") (field (name "CREATEDBY") "Judd Foster"))
      (libsource (lib "Component Library") (part "Switch,Tactile,SPST-NO,SMD,H4.3"))
    )
    (comp (ref "SW9")
      (value "PTS645SK43SMTR92 LFS")
      (footprint "C&K_PTS645SK43SMTR92 LFS")
      (description "Tactile Switch SPST-NO Top Actuated Surface Mount")
      (fields (field (name "VENDOR 1 PART NUMBER") "CKN9084CT-ND") (field (name "CREATEDBY") "Judd Foster"))
      (libsource (lib "Component Library") (part "Switch,Tactile,SPST-NO,SMD,H4.3"))
    )
    (comp (ref "SW10")
      (value "PTS645SK43SMTR92 LFS")
      (footprint "C&K_PTS645SK43SMTR92 LFS")
      (description "Tactile Switch SPST-NO Top Actuated Surface Mount")
      (fields (field (name "VENDOR 1 PART NUMBER") "CKN9084CT-ND") (field (name "CREATEDBY") "Judd Foster"))
      (libsource (lib "Component Library") (part "Switch,Tactile,SPST-NO,SMD,H4.3"))
    )
    (comp (ref "U16")
      (value "TPD4E05U06DQAR")
      (footprint "TEXASINSTRUMENTS_PKG_DQA0009A")
      (description "2.5A@8/20us 14V 40W@8/20us 6.5V Unidirectional 5.5V USON-10(1x2.5) TVS Diodes ROHS")
      (fields (field (name "VENDOR 1 PART NUMBER") "C138714") (field (name "CREATEDBY") "Judd Foster"))
      (libsource (lib "Component Library") (part "TPD4E05U06DQAR"))
    )
    (comp (ref "U18")
      (value "TXU0104PWR")
      (footprint "SOP65P640X120-14N")
      (description "General Purpose Amplifier Circuit Rail-to-Rail 8-VSSOP")
      (fields
        (field (name "VENDOR 1 PART NUMBER") "296-TXU0104PWRCT-ND")
        (field (name "CREATEDBY") "Judd Foster")
      )
      (libsource (lib "Component Library") (part "TXU0104PWR"))
    )
    (comp (ref "U19")
      (value "TXB0108PWR")
      (footprint "TEXASINSTRUMENTS_PKG_PW0020A")
      (description "100Mbps 1 8 TSSOP-20 Translators, Level Shifters ROHS")
      (fields (field (name "VENDOR 1 PART NUMBER") "C53406") (field (name "CREATEDBY") "Judd Foster"))
      (libsource (lib "Component Library") (part "TXB0108PWR"))
    )
  )
  (nets
    (net (code "6") (name "+3V3") (class "Default")
      (node (ref "C80") (pin "2") (pinfunction "2_2") (pintype "passive"))
      (node (ref "C82") (pin "2") (pinfunction "2_2") (pintype "passive"))
      (node (ref "R154") (pin "2") (pinfunction "2_2") (pintype "passive"))
      (node (ref "R155") (pin "2") (pinfunction "2_2") (pintype "passive"))
      (node (ref "R156") (pin "2") (pinfunction "2_2") (pintype "passive"))
      (node (ref "R157") (pin "2") (pinfunction "2_2") (pintype "passive"))
      (node (ref "R158") (pin "2") (pinfunction "2_2") (pintype "passive"))
      (node (ref "R159") (pin "2") (pinfunction "2_2") (pintype "passive"))
      (node (ref "R160") (pin "2") (pinfunction "2_2") (pintype "passive"))
      (node (ref "R161") (pin "2") (pinfunction "2_2") (pintype "passive"))
      (node (ref "R172") (pin "2") (pinfunction "2_2") (pintype "passive"))
      (node (ref "R182") (pin "2") (pinfunction "2_2") (pintype "passive"))
      (node (ref "U18") (pin "1") (pinfunction "VCCA_1") (pintype "power_in"))
      (node (ref "U19") (pin "2") (pinfunction "VCCA_2") (pintype "power_in"))
    )
    (net (code "7") (name "+5V0") (class "Default")
      (node (ref "C70") (pin "2") (pinfunction "2_2") (pintype "passive"))
      (node (ref "C79") (pin "2") (pinfunction "2_2") (pintype "passive"))
      (node (ref "C81") (pin "2") (pinfunction "2_2") (pintype "passive"))
      (node (ref "J8") (pin "8") (pinfunction "8_8") (pintype "passive"))
      (node (ref "R132") (pin "2") (pinfunction "2_2") (pintype "passive"))
      (node (ref "R136") (pin "3") (pinfunction "3_3") (pintype "passive"))
      (node (ref "R185") (pin "2") (pinfunction "2_2") (pintype "passive"))
      (node (ref "U18") (pin "14") (pinfunction "VCCB_14") (pintype "power_in"))
      (node (ref "U19") (pin "19") (pinfunction "VCCB_19") (pintype "power_in"))
    )
    (net (code "8") (name "/BKLT") (class "Default")
      (node (ref "U18") (pin "5") (pinfunction "A4_5") (pintype "input"))
    )
    (net (code "9") (name "/BTN.B1") (class "Default")
      (node (ref "R154") (pin "1") (pinfunction "1_1") (pintype "passive"))
      (node (ref "SW3") (pin "3") (pinfunction "3_3") (pintype "passive"))
      (node (ref "SW3") (pin "4") (pinfunction "4_4") (pintype "passive"))
    )
    (net (code "10") (name "/BTN.B2") (class "Default")
      (node (ref "R155") (pin "1") (pinfunction "1_1") (pintype "passive"))
      (node (ref "SW5") (pin "3") (pinfunction "3_3") (pintype "passive"))
      (node (ref "SW5") (pin "4") (pinfunction "4_4") (pintype "passive"))
    )
    (net (code "11") (name "/BTN.B3") (class "Default")
      (node (ref "R156") (pin "1") (pinfunction "1_1") (pintype "passive"))
      (node (ref "SW8") (pin "3") (pinfunction "3_3") (pintype "passive"))
      (node (ref "SW8") (pin "4") (pinfunction "4_4") (pintype "passive"))
    )
    (net (code "12") (name "/BTN.B4") (class "Default")
      (node (ref "R157") (pin "1") (pinfunction "1_1") (pintype "passive"))
      (node (ref "SW9") (pin "3") (pinfunction "3_3") (pintype "passive"))
      (node (ref "SW9") (pin "4") (pinfunction "4_4") (pintype "passive"))
    )
    (net (code "13") (name "/BTN.B5") (class "Default")
      (node (ref "R161") (pin "1") (pinfunction "1_1") (pintype "passive"))
      (node (ref "SW4") (pin "3") (pinfunction "3_3") (pintype "passive"))
      (node (ref "SW4") (pin "4") (pinfunction "4_4") (pintype "passive"))
    )
    (net (code "14") (name "/BTN.B6") (class "Default")
      (node (ref "R160") (pin "1") (pinfunction "1_1") (pintype "passive"))
      (node (ref "SW6") (pin "3") (pinfunction "3_3") (pintype "passive"))
      (node (ref "SW6") (pin "4") (pinfunction "4_4") (pintype "passive"))
    )
    (net (code "15") (name "/BTN.B7") (class "Default")
      (node (ref "R159") (pin "1") (pinfunction "1_1") (pintype "passive"))
      (node (ref "SW7") (pin "3") (pinfunction "3_3") (pintype "passive"))
      (node (ref "SW7") (pin "4") (pinfunction "4_4") (pintype "passive"))
    )
    (net (code "16") (name "/BTN.B8") (class "Default")
      (node (ref "R158") (pin "1") (pinfunction "1_1") (pintype "passive"))
      (node (ref "SW10") (pin "3") (pinfunction "3_3") (pintype "passive"))
      (node (ref "SW10") (pin "4") (pinfunction "4_4") (pintype "passive"))
    )
    (net (code "17") (name "/DB0") (class "Default")
      (node (ref "U19") (pin "1") (pinfunction "A1_1") (pintype "bidirectional"))
    )
    (net (code "18") (name "/DB1") (class "Default")
      (node (ref "U19") (pin "3") (pinfunction "A2_3") (pintype "bidirectional"))
    )
    (net (code "19") (name "/DB2") (class "Default")
      (node (ref "U19") (pin "4") (pinfunction "A3_4") (pintype "bidirectional"))
    )
    (net (code "20") (name "/DB3") (class "Default")
      (node (ref "U19") (pin "5") (pinfunction "A4_5") (pintype "bidirectional"))
    )
    (net (code "21") (name "/DB4") (class "Default")
      (node (ref "U19") (pin "6") (pinfunction "A5_6") (pintype "bidirectional"))
    )
    (net (code "22") (name "/DB5") (class "Default")
      (node (ref "U19") (pin "7") (pinfunction "A6_7") (pintype "bidirectional"))
    )
    (net (code "23") (name "/DB6") (class "Default")
      (node (ref "U19") (pin "8") (pinfunction "A7_8") (pintype "bidirectional"))
    )
    (net (code "24") (name "/DB7") (class "Default")
      (node (ref "U19") (pin "9") (pinfunction "A8_9") (pintype "bidirectional"))
    )
    (net (code "25") (name "/E") (class "Default")
      (node (ref "U18") (pin "4") (pinfunction "A3_4") (pintype "input"))
    )
    (net (code "26") (name "/FTDI.RXD") (class "Default")
      (node (ref "D27") (pin "1") (pinfunction "K_1") (pintype "passive"))
      (node (ref "J6") (pin "5") (pinfunction "5_5") (pintype "passive"))
      (node (ref "R174") (pin "1") (pinfunction "1_1") (pintype "passive"))
    )
    (net (code "27") (name "/FTDI.TXD") (class "Default")
      (node (ref "D28") (pin "1") (pinfunction "K_1") (pintype "passive"))
      (node (ref "J6") (pin "4") (pinfunction "4_4") (pintype "passive"))
      (node (ref "R175") (pin "1") (pinfunction "1_1") (pintype "passive"))
    )
    (net (code "28") (name "/OE") (class "Default")
      (node (ref "R183") (pin "2") (pinfunction "2_2") (pintype "passive"))
      (node (ref "U18") (pin "8") (pinfunction "OE_8") (pintype "input"))
      (node (ref "U19") (pin "10") (pinfunction "OE_10") (pintype "input"))
    )
    (net (code "29") (name "/PROG.RST_N") (class "Default")
      (node (ref "R173") (pin "1") (pinfunction "1_1") (pintype "passive"))
    )
    (net (code "30") (name "/PROG.SWCLK") (class "Default")
      (node (ref "R169") (pin "1") (pinfunction "1_1") (pintype "passive"))
    )
    (net (code "31") (name "/PROG.SWDIO") (class "Default")
      (node (ref "R168") (pin "1") (pinfunction "1_1") (pintype "passive"))
    )
    (net (code "32") (name "/PROG.SWO") (class "Default")
      (node (ref "R170") (pin "1") (pinfunction "1_1") (pintype "passive"))
    )
    (net (code "33") (name "/PROG.TDI") (class "Default")
      (node (ref "R171") (pin "1") (pinfunction "1_1") (pintype "passive"))
    )
    (net (code "34") (name "/RS") (class "Default")
      (node (ref "U18") (pin "2") (pinfunction "A1_2") (pintype "input"))
    )
    (net (code "35") (name "/R{slash}W") (class "Default")
      (node (ref "U18") (pin "3") (pinfunction "A2_3") (pintype "input"))
    )
    (net (code "36") (name "/UART.RXD") (class "Default")
      (node (ref "R175") (pin "2") (pinfunction "2_2") (pintype "passive"))
    )
    (net (code "37") (name "/UART.TXD") (class "Default")
      (node (ref "R174") (pin "2") (pinfunction "2_2") (pintype "passive"))
    )
    (net (code "38") (name "/USB.D_N") (class "Default")
      (node (ref "J4") (pin "A7") (pinfunction "DN1_A7") (pintype "passive"))
      (node (ref "J4") (pin "B7") (pinfunction "DN2_B7") (pintype "passive"))
      (node (ref "U16") (pin "2") (pinfunction "D1-_2") (pintype "passive"))
      (node (ref "U16") (pin "9") (pinfunction "NC_9") (pintype "passive"))
    )
    (net (code "39") (name "/USB.D_P") (class "Default")
      (node (ref "J4") (pin "A6") (pinfunction "DP1_A6") (pintype "passive"))
      (node (ref "J4") (pin "B6") (pinfunction "DP2_B6") (pintype "passive"))
      (node (ref "U16") (pin "1") (pinfunction "D1+_1") (pintype "passive"))
      (node (ref "U16") (pin "10") (pinfunction "NC_10") (pintype "passive"))
    )
    (net (code "45") (name "COM") (class "Default")
      (node (ref "C2") (pin "1") (pinfunction "1_1") (pintype "passive"))
      (node (ref "C70") (pin "1") (pinfunction "1_1") (pintype "passive"))
      (node (ref "C77") (pin "1") (pinfunction "1_1") (pintype "passive"))
      (node (ref "C79") (pin "1") (pinfunction "1_1") (pintype "passive"))
      (node (ref "C80") (pin "1") (pinfunction "1_1") (pintype "passive"))
      (node (ref "C81") (pin "1") (pinfunction "1_1") (pintype "passive"))
      (node (ref "C82") (pin "1") (pinfunction "1_1") (pintype "passive"))
      (node (ref "D18") (pin "2") (pinfunction "A_2") (pintype "passive"))
      (node (ref "D19") (pin "2") (pinfunction "A_2") (pintype "passive"))
      (node (ref "D22") (pin "1") (pinfunction "K_1") (pintype "passive"))
      (node (ref "D23") (pin "1") (pinfunction "K_1") (pintype "passive"))
      (node (ref "D24") (pin "1") (pinfunction "K_1") (pintype "passive"))
      (node (ref "D25") (pin "1") (pinfunction "K_1") (pintype "passive"))
      (node (ref "D26") (pin "1") (pinfunction "K_1") (pintype "passive"))
      (node (ref "D27") (pin "2") (pinfunction "A_2") (pintype "passive"))
      (node (ref "D28") (pin "2") (pinfunction "A_2") (pintype "passive"))
      (node (ref "J4") (pin "0") (pinfunction "SH_0") (pintype "passive"))
      (node (ref "J4") (pin "A1/B12") (pinfunction "GND_A1/B12") (pintype "passive"))
      (node (ref "J4") (pin "A12/B1") (pinfunction "GND_A12/B1") (pintype "passive"))
      (node (ref "J5") (pin "1") (pinfunction "1_1") (pintype "passive"))
      (node (ref "J5") (pin "3") (pinfunction "3_3") (pintype "passive"))
      (node (ref "J5") (pin "5") (pinfunction "5_5") (pintype "passive"))
      (node (ref "J5") (pin "9") (pinfunction "9_9") (pintype "passive"))
      (node (ref "J6") (pin "1") (pinfunction "1_1") (pintype "passive"))
      (node (ref "J8") (pin "10") (pinfunction "10_10") (pintype "passive"))
      (node (ref "Q10") (pin "2") (pinfunction "S_2") (pintype "passive"))
      (node (ref "R129") (pin "1") (pinfunction "1_1") (pintype "passive"))
      (node (ref "R130") (pin "1") (pinfunction "1_1") (pintype "passive"))
      (node (ref "R136") (pin "1") (pinfunction "1_1") (pintype "passive"))
      (node (ref "R153") (pin "1") (pinfunction "1_1") (pintype "passive"))
      (node (ref "R183") (pin "1") (pinfunction "1_1") (pintype "passive"))
      (node (ref "SW10") (pin "1") (pinfunction "1_1") (pintype "passive"))
      (node (ref "SW10") (pin "2") (pinfunction "2_2") (pintype "passive"))
      (node (ref "SW3") (pin "1") (pinfunction "1_1") (pintype "passive"))
      (node (ref "SW3") (pin "2") (pinfunction "2_2") (pintype "passive"))
      (node (ref "SW4") (pin "1") (pinfunction "1_1") (pintype "passive"))
      (node (ref "SW4") (pin "2") (pinfunction "2_2") (pintype "passive"))
      (node (ref "SW5") (pin "1") (pinfunction "1_1") (pintype "passive"))
      (node (ref "SW5") (pin "2") (pinfunction "2_2") (pintype "passive"))
      (node (ref "SW6") (pin "1") (pinfunction "1_1") (pintype "passive"))
      (node (ref "SW6") (pin "2") (pinfunction "2_2") (pintype "passive"))
      (node (ref "SW7") (pin "1") (pinfunction "1_1") (pintype "passive"))
      (node (ref "SW7") (pin "2") (pinfunction "2_2") (pintype "passive"))
      (node (ref "SW8") (pin "1") (pinfunction "1_1") (pintype "passive"))
      (node (ref "SW8") (pin "2") (pinfunction "2_2") (pintype "passive"))
      (node (ref "SW9") (pin "1") (pinfunction "1_1") (pintype "passive"))
      (node (ref "SW9") (pin "2") (pinfunction "2_2") (pintype "passive"))
      (node (ref "U16") (pin "3") (pinfunction "GND_3") (pintype "power_in"))
      (node (ref "U16") (pin "4") (pinfunction "D2+_4") (pintype "passive"))
      (node (ref "U16") (pin "5") (pinfunction "D2-_5") (pintype "passive"))
      (node (ref "U16") (pin "6") (pinfunction "NC_6") (pintype "passive"))
      (node (ref "U16") (pin "7") (pinfunction "NC_7") (pintype "passive"))
      (node (ref "U16") (pin "8") (pinfunction "GND_8") (pintype "power_in"))
      (node (ref "U18") (pin "7") (pinfunction "GND_7") (pintype "power_in"))
      (node (ref "U19") (pin "11") (pinfunction "GND_11") (pintype "power_in"))
    )
    (net (code "46") (name "Net-(D18-K)") (class "Default")
      (node (ref "C2") (pin "2") (pinfunction "2_2") (pintype "passive"))
      (node (ref "C77") (pin "2") (pinfunction "2_2") (pintype "passive"))
      (node (ref "D18") (pin "1") (pinfunction "K_1") (pintype "passive"))
      (node (ref "D19") (pin "1") (pinfunction "K_1") (pintype "passive"))
      (node (ref "FB3") (pin "1") (pinfunction "1_1") (pintype "passive"))
      (node (ref "FB4") (pin "1") (pinfunction "1_1") (pintype "passive"))
      (node (ref "J4") (pin "A4/B9") (pinfunction "VBUS_A4/B9") (pintype "passive"))
      (node (ref "J4") (pin "A9/B4") (pinfunction "VBUS_A9/B4") (pintype "passive"))
    )
    (net (code "47") (name "Net-(D22-A)") (class "Default")
      (node (ref "D22") (pin "2") (pinfunction "A_2") (pintype "passive"))
      (node (ref "J5") (pin "2") (pinfunction "2_2") (pintype "passive"))
      (node (ref "R168") (pin "2") (pinfunction "2_2") (pintype "passive"))
    )
    (net (code "48") (name "Net-(D23-A)") (class "Default")
      (node (ref "D23") (pin "2") (pinfunction "A_2") (pintype "passive"))
      (node (ref "J5") (pin "4") (pinfunction "4_4") (pintype "passive"))
      (node (ref "R169") (pin "2") (pinfunction "2_2") (pintype "passive"))
    )
    (net (code "49") (name "Net-(D24-A)") (class "Default")
      (node (ref "D24") (pin "2") (pinfunction "A_2") (pintype "passive"))
      (node (ref "J5") (pin "6") (pinfunction "6_6") (pintype "passive"))
      (node (ref "R170") (pin "2") (pinfunction "2_2") (pintype "passive"))
    )
    (net (code "50") (name "Net-(D25-A)") (class "Default")
      (node (ref "D25") (pin "2") (pinfunction "A_2") (pintype "passive"))
      (node (ref "J5") (pin "8") (pinfunction "8_8") (pintype "passive"))
      (node (ref "R171") (pin "2") (pinfunction "2_2") (pintype "passive"))
    )
    (net (code "51") (name "Net-(D26-A)") (class "Default")
      (node (ref "D26") (pin "2") (pinfunction "A_2") (pintype "passive"))
      (node (ref "J5") (pin "10") (pinfunction "10_10") (pintype "passive"))
      (node (ref "R173") (pin "2") (pinfunction "2_2") (pintype "passive"))
    )
    (net (code "52") (name "Net-(J4-CC1)") (class "Default")
      (node (ref "J4") (pin "A5") (pinfunction "CC1_A5") (pintype "passive"))
      (node (ref "R130") (pin "2") (pinfunction "2_2") (pintype "passive"))
    )
    (net (code "53") (name "Net-(J4-CC2)") (class "Default")
      (node (ref "J4") (pin "B5") (pinfunction "CC2_B5") (pintype "passive"))
      (node (ref "R129") (pin "2") (pinfunction "2_2") (pintype "passive"))
    )
    (net (code "54") (name "Net-(J5-Pad7)") (class "Default")
      (node (ref "J5") (pin "7") (pinfunction "7_7") (pintype "passive"))
      (node (ref "R172") (pin "1") (pinfunction "1_1") (pintype "passive"))
    )
    (net (code "55") (name "Net-(J6-Pad3)") (class "Default")
      (node (ref "J6") (pin "3") (pinfunction "3_3") (pintype "passive"))
      (node (ref "R182") (pin "1") (pinfunction "1_1") (pintype "passive"))
    )
    (net (code "56") (name "Net-(J8-Pad1)") (class "Default")
      (node (ref "J8") (pin "1") (pinfunction "1_1") (pintype "passive"))
      (node (ref "R137") (pin "1") (pinfunction "1_1") (pintype "passive"))
    )
    (net (code "57") (name "Net-(J8-Pad2)") (class "Default")
      (node (ref "J8") (pin "2") (pinfunction "2_2") (pintype "passive"))
      (node (ref "R134") (pin "1") (pinfunction "1_1") (pintype "passive"))
    )
    (net (code "58") (name "Net-(J8-Pad3)") (class "Default")
      (node (ref "J8") (pin "3") (pinfunction "3_3") (pintype "passive"))
      (node (ref "R139") (pin "1") (pinfunction "1_1") (pintype "passive"))
    )
    (net (code "59") (name "Net-(J8-Pad4)") (class "Default")
      (node (ref "J8") (pin "4") (pinfunction "4_4") (pintype "passive"))
      (node (ref "R133") (pin "1") (pinfunction "1_1") (pintype "passive"))
    )
    (net (code "60") (name "Net-(J8-Pad5)") (class "Default")
      (node (ref "J8") (pin "5") (pinfunction "5_5") (pintype "passive"))
      (node (ref "R141") (pin "1") (pinfunction "1_1") (pintype "passive"))
    )
    (net (code "61") (name "Net-(J8-Pad6)") (class "Default")
      (node (ref "J8") (pin "6") (pinfunction "6_6") (pintype "passive"))
      (node (ref "R131") (pin "1") (pinfunction "1_1") (pintype "passive"))
    )
    (net (code "62") (name "Net-(J8-Pad7)") (class "Default")
      (node (ref "J8") (pin "7") (pinfunction "7_7") (pintype "passive"))
      (node (ref "R143") (pin "1") (pinfunction "1_1") (pintype "passive"))
    )
    (net (code "63") (name "Net-(J8-Pad9)") (class "Default")
      (node (ref "J8") (pin "9") (pinfunction "9_9") (pintype "passive"))
      (node (ref "R145") (pin "1") (pinfunction "1_1") (pintype "passive"))
    )
    (net (code "64") (name "Net-(J8-Pad11)") (class "Default")
      (node (ref "J8") (pin "11") (pinfunction "11_11") (pintype "passive"))
      (node (ref "R147") (pin "1") (pinfunction "1_1") (pintype "passive"))
    )
    (net (code "65") (name "Net-(J8-Pad12)") (class "Default")
      (node (ref "J8") (pin "12") (pinfunction "12_12") (pintype "passive"))
      (node (ref "R136") (pin "2") (pinfunction "2_2") (pintype "passive"))
    )
    (net (code "66") (name "Net-(J8-Pad13)") (class "Default")
      (node (ref "J8") (pin "13") (pinfunction "13_13") (pintype "passive"))
      (node (ref "R149") (pin "1") (pinfunction "1_1") (pintype "passive"))
    )
    (net (code "67") (name "Net-(J8-Pad14)") (class "Default")
      (node (ref "J8") (pin "14") (pinfunction "14_14") (pintype "passive"))
      (node (ref "R132") (pin "1") (pinfunction "1_1") (pintype "passive"))
      (node (ref "R185") (pin "1") (pinfunction "1_1") (pintype "passive"))
    )
    (net (code "68") (name "Net-(J8-Pad15)") (class "Default")
      (node (ref "J8") (pin "15") (pinfunction "15_15") (pintype "passive"))
      (node (ref "R151") (pin "1") (pinfunction "1_1") (pintype "passive"))
    )
    (net (code "69") (name "Net-(Q10-D)") (class "Default")
      (node (ref "J8") (pin "16") (pinfunction "16_16") (pintype "passive"))
      (node (ref "Q10") (pin "3") (pinfunction "D_3") (pintype "passive"))
    )
    (net (code "70") (name "Net-(Q10-G)") (class "Default")
      (node (ref "Q10") (pin "1") (pinfunction "G_1") (pintype "passive"))
      (node (ref "R135") (pin "1") (pinfunction "1_1") (pintype "passive"))
      (node (ref "R153") (pin "2") (pinfunction "2_2") (pintype "passive"))
    )
    (net (code "71") (name "Net-(U18-B1Y)") (class "Default")
      (node (ref "R131") (pin "2") (pinfunction "2_2") (pintype "passive"))
      (node (ref "U18") (pin "13") (pinfunction "B1Y_13") (pintype "output"))
    )
    (net (code "72") (name "Net-(U18-B2Y)") (class "Default")
      (node (ref "R133") (pin "2") (pinfunction "2_2") (pintype "passive"))
      (node (ref "U18") (pin "12") (pinfunction "B2Y_12") (pintype "output"))
    )
    (net (code "73") (name "Net-(U18-B3Y)") (class "Default")
      (node (ref "R134") (pin "2") (pinfunction "2_2") (pintype "passive"))
      (node (ref "U18") (pin "11") (pinfunction "B3Y_11") (pintype "output"))
    )
    (net (code "74") (name "Net-(U18-B4Y)") (class "Default")
      (node (ref "R135") (pin "2") (pinfunction "2_2") (pintype "passive"))
      (node (ref "U18") (pin "10") (pinfunction "B4Y_10") (pintype "output"))
    )
    (net (code "75") (name "Net-(U19-B1)") (class "Default")
      (node (ref "R137") (pin "2") (pinfunction "2_2") (pintype "passive"))
      (node (ref "U19") (pin "20") (pinfunction "B1_20") (pintype "bidirectional"))
    )
    (net (code "76") (name "Net-(U19-B2)") (class "Default")
      (node (ref "R139") (pin "2") (pinfunction "2_2") (pintype "passive"))
      (node (ref "U19") (pin "18") (pinfunction "B2_18") (pintype "bidirectional"))
    )
    (net (code "77") (name "Net-(U19-B3)") (class "Default")
      (node (ref "R141") (pin "2") (pinfunction "2_2") (pintype "passive"))
      (node (ref "U19") (pin "17") (pinfunction "B3_17") (pintype "bidirectional"))
    )
    (net (code "78") (name "Net-(U19-B4)") (class "Default")
      (node (ref "R143") (pin "2") (pinfunction "2_2") (pintype "passive"))
      (node (ref "U19") (pin "16") (pinfunction "B4_16") (pintype "bidirectional"))
    )
    (net (code "79") (name "Net-(U19-B5)") (class "Default")
      (node (ref "R145") (pin "2") (pinfunction "2_2") (pintype "passive"))
      (node (ref "U19") (pin "15") (pinfunction "B5_15") (pintype "bidirectional"))
    )
    (net (code "80") (name "Net-(U19-B6)") (class "Default")
      (node (ref "R147") (pin "2") (pinfunction "2_2") (pintype "passive"))
      (node (ref "U19") (pin "14") (pinfunction "B6_14") (pintype "bidirectional"))
    )
    (net (code "81") (name "Net-(U19-B7)") (class "Default")
      (node (ref "R149") (pin "2") (pinfunction "2_2") (pintype "passive"))
      (node (ref "U19") (pin "13") (pinfunction "B7_13") (pintype "bidirectional"))
    )
    (net (code "82") (name "Net-(U19-B8)") (class "Default")
      (node (ref "R151") (pin "2") (pinfunction "2_2") (pintype "passive"))
      (node (ref "U19") (pin "12") (pinfunction "B8_12") (pintype "bidirectional"))
    )
    (net (code "83") (name "VUSB") (class "Default")
      (node (ref "FB3") (pin "2") (pinfunction "2_2") (pintype "passive"))
      (node (ref "FB4") (pin "2") (pinfunction "2_2") (pintype "passive"))
    )
    (net (code "84") (name "unconnected-(J4-SBU1-PadA8)") (class "Default")
      (node (ref "J4") (pin "A8") (pinfunction "SBU1_A8") (pintype "passive"))
    )
    (net (code "85") (name "unconnected-(J4-SBU2-PadB8)") (class "Default")
      (node (ref "J4") (pin "B8") (pinfunction "SBU2_B8") (pintype "passive"))
    )
    (net (code "86") (name "unconnected-(J6-Pad2)") (class "Default")
      (node (ref "J6") (pin "2") (pinfunction "2_2") (pintype "passive"))
    )
    (net (code "87") (name "unconnected-(J6-Pad6)") (class "Default")
      (node (ref "J6") (pin "6") (pinfunction "6_6") (pintype "passive"))
    )
    (net (code "88") (name "unconnected-(U18-NC-Pad6)") (class "Default")
      (node (ref "U18") (pin "6") (pinfunction "NC_6") (pintype "passive"))
    )
    (net (code "89") (name "unconnected-(U18-NC-Pad9)") (class "Default")
      (node (ref "U18") (pin "9") (pinfunction "NC_9") (pintype "passive"))
    )
  )
)
